# Adafruit_NeoPixel_Ring_24_B_-_Holder_3.net
KiCad netlist of a schematic drawn in EAGLE
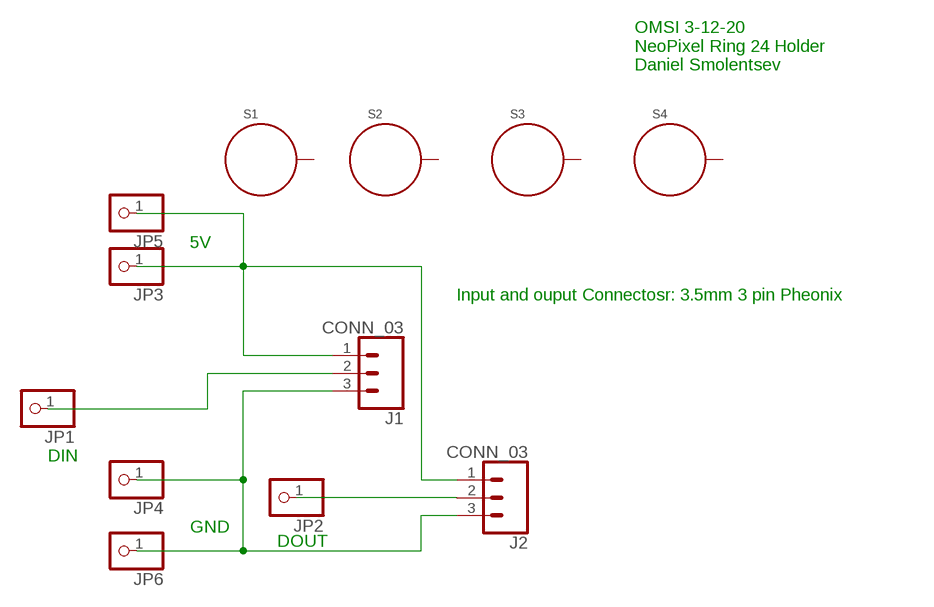
[diagram p0: schematic, sheet 1]

(export (version "E")
  (design (tool "Eeschema 10.0.6"))
  (components
    (comp (ref "J1")
      (value "CONN_03")
      (footprint "eagle-import:1X03_3.5MM_RA")
      (libsource (lib "eagle-import") (part "CONN_03"))
    )
    (comp (ref "J2")
      (value "CONN_03")
      (footprint "eagle-import:1X03_3.5MM_RA")
      (libsource (lib "eagle-import") (part "CONN_03"))
    )
    (comp (ref "JP1")
      (value "PINHD-1X1CB")
      (footprint "eagle-import:1X01-CLEANBIG")
      (libsource (lib "eagle-import") (part "PINHD-1X1CB"))
    )
    (comp (ref "JP2")
      (value "PINHD-1X1CB")
      (footprint "eagle-import:1X01-CLEANBIG")
      (libsource (lib "eagle-import") (part "PINHD-1X1CB"))
    )
    (comp (ref "JP3")
      (value "PINHD-1X1CB")
      (footprint "eagle-import:1X01-CLEANBIG")
      (libsource (lib "eagle-import") (part "PINHD-1X1CB"))
    )
    (comp (ref "JP4")
      (value "PINHD-1X1CB")
      (footprint "eagle-import:1X01-CLEANBIG")
      (libsource (lib "eagle-import") (part "PINHD-1X1CB"))
    )
    (comp (ref "JP5")
      (value "PINHD-1X1CB")
      (footprint "eagle-import:1X01-CLEANBIG")
      (libsource (lib "eagle-import") (part "PINHD-1X1CB"))
    )
    (comp (ref "JP6")
      (value "PINHD-1X1CB")
      (footprint "eagle-import:1X01-CLEANBIG")
      (libsource (lib "eagle-import") (part "PINHD-1X1CB"))
    )
    (comp (ref "S1")
      (value "STANDOFF_ELECTRICAL.17\"")
      (footprint "eagle-import:STANDOFF-ELECTRICAL")
      (libsource (lib "eagle-import") (part "STANDOFF_ELECTRICAL.17{dblquote}"))
    )
    (comp (ref "S2")
      (value "STANDOFF_ELECTRICAL.17\"")
      (footprint "eagle-import:STANDOFF-ELECTRICAL")
      (libsource (lib "eagle-import") (part "STANDOFF_ELECTRICAL.17{dblquote}"))
    )
    (comp (ref "S3")
      (value "STANDOFF_ELECTRICAL.17\"")
      (footprint "eagle-import:STANDOFF-ELECTRICAL")
      (libsource (lib "eagle-import") (part "STANDOFF_ELECTRICAL.17{dblquote}"))
    )
    (comp (ref "S4")
      (value "STANDOFF_ELECTRICAL.17\"")
      (footprint "eagle-import:STANDOFF-ELECTRICAL")
      (libsource (lib "eagle-import") (part "STANDOFF_ELECTRICAL.17{dblquote}"))
    )
  )
  (nets
    (net (code "1") (name "Net-(J1-Pad1)") (class "Default")
      (node (ref "J1") (pin "1") (pinfunction "1_1") (pintype "passive"))
      (node (ref "J2") (pin "1") (pinfunction "1_1") (pintype "passive"))
      (node (ref "JP3") (pin "1") (pinfunction "1_1") (pintype "passive"))
      (node (ref "JP5") (pin "1") (pinfunction "1_1") (pintype "passive"))
    )
    (net (code "2") (name "Net-(J1-Pad2)") (class "Default")
      (node (ref "J1") (pin "2") (pinfunction "2_2") (pintype "passive"))
      (node (ref "JP1") (pin "1") (pinfunction "1_1") (pintype "passive"))
    )
    (net (code "3") (name "Net-(J1-Pad3)") (class "Default")
      (node (ref "J1") (pin "3") (pinfunction "3_3") (pintype "passive"))
      (node (ref "J2") (pin "3") (pinfunction "3_3") (pintype "passive"))
      (node (ref "JP4") (pin "1") (pinfunction "1_1") (pintype "passive"))
      (node (ref "JP6") (pin "1") (pinfunction "1_1") (pintype "passive"))
    )
    (net (code "4") (name "Net-(J2-Pad2)") (class "Default")
      (node (ref "J2") (pin "2") (pinfunction "2_2") (pintype "passive"))
      (node (ref "JP2") (pin "1") (pinfunction "1_1") (pintype "passive"))
    )
    (net (code "5") (name "unconnected-(S1-P$1-PadP1)") (class "Default")
      (node (ref "S1") (pin "P1") (pinfunction "P$1_P1") (pintype "bidirectional"))
    )
    (net (code "6") (name "unconnected-(S2-P$1-PadP1)") (class "Default")
      (node (ref "S2") (pin "P1") (pinfunction "P$1_P1") (pintype "bidirectional"))
    )
    (net (code "7") (name "unconnected-(S3-P$1-PadP1)") (class "Default")
      (node (ref "S3") (pin "P1") (pinfunction "P$1_P1") (pintype "bidirectional"))
    )
    (net (code "8") (name "unconnected-(S4-P$1-PadP1)") (class "Default")
      (node (ref "S4") (pin "P1") (pinfunction "P$1_P1") (pintype "bidirectional"))
    )
  )
)
